# 8266_ultrasonic.net
KiCad netlist of a schematic drawn in EAGLE
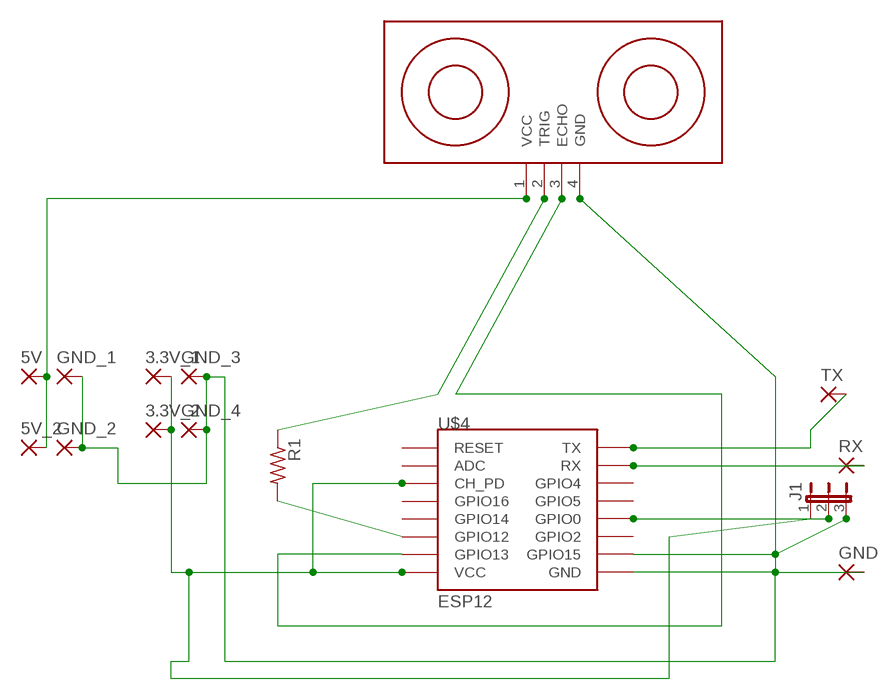
[diagram p0: schematic, sheet 1]

(export (version "E")
  (design (tool "Eeschema 10.0.6"))
  (components
    (comp (ref "3.3V_1")
      (value "2,15/1,0")
      (footprint "eagle-import:2,15_1,0")
      (libsource (lib "eagle-import") (part "2,15/1,0"))
    )
    (comp (ref "3.3V_2")
      (value "2,15/1,0")
      (footprint "eagle-import:2,15_1,0")
      (libsource (lib "eagle-import") (part "2,15/1,0"))
    )
    (comp (ref "5V")
      (value "2,15/1,0")
      (footprint "eagle-import:2,15_1,0")
      (libsource (lib "eagle-import") (part "2,15/1,0"))
    )
    (comp (ref "5V_2")
      (value "2,15/1,0")
      (footprint "eagle-import:2,15_1,0")
      (libsource (lib "eagle-import") (part "2,15/1,0"))
    )
    (comp (ref "GND")
      (value "2,15/1,0")
      (footprint "eagle-import:2,15_1,0")
      (libsource (lib "eagle-import") (part "2,15/1,0"))
    )
    (comp (ref "GND_1")
      (value "2,15/1,0")
      (footprint "eagle-import:2,15_1,0")
      (libsource (lib "eagle-import") (part "2,15/1,0"))
    )
    (comp (ref "GND_2")
      (value "2,15/1,0")
      (footprint "eagle-import:2,15_1,0")
      (libsource (lib "eagle-import") (part "2,15/1,0"))
    )
    (comp (ref "GND_3")
      (value "2,15/1,0")
      (footprint "eagle-import:2,15_1,0")
      (libsource (lib "eagle-import") (part "2,15/1,0"))
    )
    (comp (ref "GND_4")
      (value "2,15/1,0")
      (footprint "eagle-import:2,15_1,0")
      (libsource (lib "eagle-import") (part "2,15/1,0"))
    )
    (comp (ref "J1")
      (value "JP2E")
      (footprint "eagle-import:JP2")
      (libsource (lib "eagle-import") (part "JP2E"))
    )
    (comp (ref "R1")
      (value "R-US_0207/10")
      (footprint "eagle-import:0207_10")
      (libsource (lib "eagle-import") (part "R-US_0207/10"))
    )
    (comp (ref "RX")
      (value "2,15/1,0")
      (footprint "eagle-import:2,15_1,0")
      (libsource (lib "eagle-import") (part "2,15/1,0"))
    )
    (comp (ref "TX")
      (value "2,15/1,0")
      (footprint "eagle-import:2,15_1,0")
      (libsource (lib "eagle-import") (part "2,15/1,0"))
    )
    (comp (ref "U$3")
      (value "ULTRASONIC-HC-SR04#V")
      (footprint "eagle-import:ULTRASONIC-HC-SR04#V")
      (libsource (lib "eagle-import") (part "ULTRASONIC-HC-SR04#V"))
    )
    (comp (ref "U$4")
      (value "ESP12")
      (footprint "eagle-import:ESP12")
      (libsource (lib "eagle-import") (part "ESP12"))
    )
  )
  (nets
    (net (code "1") (name "Net-(3.3V_1-P)") (class "Default")
      (node (ref "3.3V_1") (pin "1") (pinfunction "P_1") (pintype "passive"))
      (node (ref "3.3V_2") (pin "1") (pinfunction "P_1") (pintype "passive"))
      (node (ref "J1") (pin "1") (pinfunction "1_1") (pintype "passive"))
      (node (ref "U$4") (pin "CH_PD") (pinfunction "CH_PD_CH_PD") (pintype "bidirectional"))
      (node (ref "U$4") (pin "VCC") (pinfunction "VCC_VCC") (pintype "bidirectional"))
    )
    (net (code "2") (name "Net-(5V-P)") (class "Default")
      (node (ref "5V") (pin "1") (pinfunction "P_1") (pintype "passive"))
      (node (ref "5V_2") (pin "1") (pinfunction "P_1") (pintype "passive"))
      (node (ref "U$3") (pin "1") (pinfunction "VCC_1") (pintype "power_in"))
    )
    (net (code "3") (name "Net-(GND-P)") (class "Default")
      (node (ref "GND") (pin "1") (pinfunction "P_1") (pintype "passive"))
      (node (ref "GND_1") (pin "1") (pinfunction "P_1") (pintype "passive"))
      (node (ref "GND_2") (pin "1") (pinfunction "P_1") (pintype "passive"))
      (node (ref "GND_3") (pin "1") (pinfunction "P_1") (pintype "passive"))
      (node (ref "GND_4") (pin "1") (pinfunction "P_1") (pintype "passive"))
      (node (ref "J1") (pin "3") (pinfunction "3_3") (pintype "passive"))
      (node (ref "U$3") (pin "4") (pinfunction "GND_4") (pintype "power_in"))
      (node (ref "U$4") (pin "GND") (pinfunction "GND_GND") (pintype "bidirectional"))
      (node (ref "U$4") (pin "GPIO15") (pinfunction "GPIO15_GPIO15") (pintype "bidirectional"))
    )
    (net (code "4") (name "Net-(J1-Pad2)") (class "Default")
      (node (ref "J1") (pin "2") (pinfunction "2_2") (pintype "passive"))
      (node (ref "U$4") (pin "GPIO0") (pinfunction "GPIO0_GPIO0") (pintype "bidirectional"))
    )
    (net (code "5") (name "Net-(R1-Pad2)") (class "Default")
      (node (ref "R1") (pin "2") (pinfunction "2_2") (pintype "passive"))
      (node (ref "U$4") (pin "GPIO12") (pinfunction "GPIO12_GPIO12") (pintype "bidirectional"))
    )
    (net (code "6") (name "Net-(RX-P)") (class "Default")
      (node (ref "RX") (pin "1") (pinfunction "P_1") (pintype "passive"))
      (node (ref "U$4") (pin "RX") (pinfunction "RX_RX") (pintype "bidirectional"))
    )
    (net (code "7") (name "Net-(TX-P)") (class "Default")
      (node (ref "TX") (pin "1") (pinfunction "P_1") (pintype "passive"))
      (node (ref "U$4") (pin "TX") (pinfunction "TX_TX") (pintype "bidirectional"))
    )
    (net (code "8") (name "Net-(U$3-ECHO)") (class "Default")
      (node (ref "U$3") (pin "3") (pinfunction "ECHO_3") (pintype "output"))
      (node (ref "U$4") (pin "GPIO13") (pinfunction "GPIO13_GPIO13") (pintype "bidirectional"))
    )
    (net (code "9") (name "Net-(U$3-TRIG)") (class "Default")
      (node (ref "R1") (pin "1") (pinfunction "1_1") (pintype "passive"))
      (node (ref "U$3") (pin "2") (pinfunction "TRIG_2") (pintype "input"))
    )
    (net (code "10") (name "unconnected-(U$4-PadADC)") (class "Default")
      (node (ref "U$4") (pin "ADC") (pinfunction "ADC_ADC") (pintype "bidirectional"))
    )
    (net (code "11") (name "unconnected-(U$4-PadGPIO2)") (class "Default")
      (node (ref "U$4") (pin "GPIO2") (pinfunction "GPIO2_GPIO2") (pintype "bidirectional"))
    )
    (net (code "12") (name "unconnected-(U$4-PadGPIO4)") (class "Default")
      (node (ref "U$4") (pin "GPIO4") (pinfunction "GPIO4_GPIO4") (pintype "bidirectional"))
    )
    (net (code "13") (name "unconnected-(U$4-PadGPIO5)") (class "Default")
      (node (ref "U$4") (pin "GPIO5") (pinfunction "GPIO5_GPIO5") (pintype "bidirectional"))
    )
    (net (code "14") (name "unconnected-(U$4-PadGPIO14)") (class "Default")
      (node (ref "U$4") (pin "GPIO14") (pinfunction "GPIO14_GPIO14") (pintype "bidirectional"))
    )
    (net (code "15") (name "unconnected-(U$4-PadGPIO16)") (class "Default")
      (node (ref "U$4") (pin "GPIO16") (pinfunction "GPIO16_GPIO16") (pintype "bidirectional"))
    )
    (net (code "16") (name "unconnected-(U$4-PadRESET)") (class "Default")
      (node (ref "U$4") (pin "RESET") (pinfunction "RESET_RESET") (pintype "bidirectional"))
    )
  )
)
